# slave.net
KiCad netlist of a schematic drawn in EAGLE
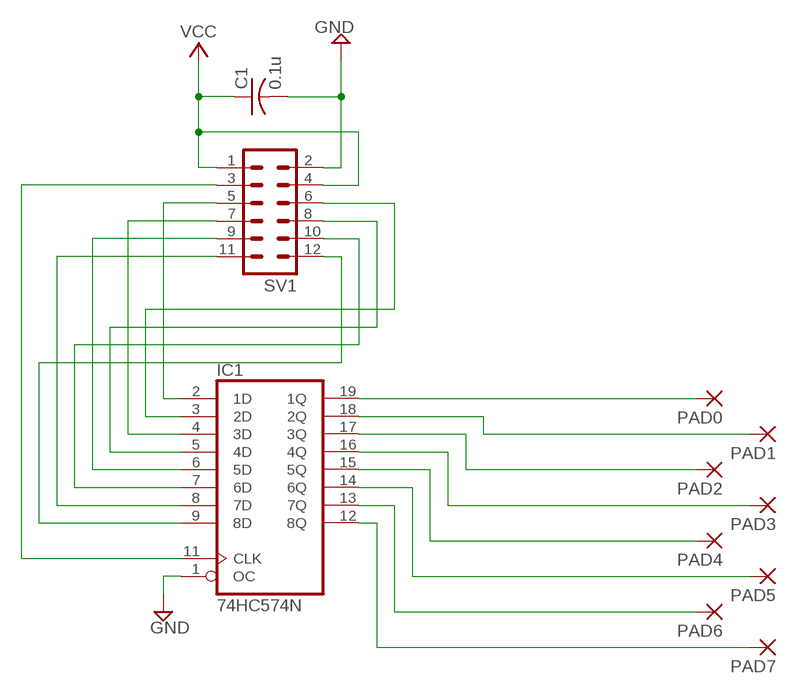
[diagram p0: schematic, sheet 1]

(export (version "E")
  (design (tool "Eeschema 10.0.6"))
  (components
    (comp (ref "C1")
      (value "0.1u")
      (footprint "eagle-import:C0805")
      (libsource (lib "eagle-import") (part "C-USC0805"))
    )
    (comp (ref "IC1")
      (value "74HC574N")
      (footprint "eagle-import:DIL20")
      (libsource (lib "eagle-import") (part "74574NHC"))
    )
    (comp (ref "PAD0")
      (value "2,54/0,8")
      (footprint "eagle-import:2,54_0,8")
      (libsource (lib "eagle-import") (part "2,54/0,8"))
    )
    (comp (ref "PAD1")
      (value "2,54/0,8")
      (footprint "eagle-import:2,54_0,8")
      (libsource (lib "eagle-import") (part "2,54/0,8"))
    )
    (comp (ref "PAD2")
      (value "2,54/0,8")
      (footprint "eagle-import:2,54_0,8")
      (libsource (lib "eagle-import") (part "2,54/0,8"))
    )
    (comp (ref "PAD3")
      (value "2,54/0,8")
      (footprint "eagle-import:2,54_0,8")
      (libsource (lib "eagle-import") (part "2,54/0,8"))
    )
    (comp (ref "PAD4")
      (value "2,54/0,8")
      (footprint "eagle-import:2,54_0,8")
      (libsource (lib "eagle-import") (part "2,54/0,8"))
    )
    (comp (ref "PAD5")
      (value "2,54/0,8")
      (footprint "eagle-import:2,54_0,8")
      (libsource (lib "eagle-import") (part "2,54/0,8"))
    )
    (comp (ref "PAD6")
      (value "2,54/0,8")
      (footprint "eagle-import:2,54_0,8")
      (libsource (lib "eagle-import") (part "2,54/0,8"))
    )
    (comp (ref "PAD7")
      (value "2,54/0,8")
      (footprint "eagle-import:2,54_0,8")
      (libsource (lib "eagle-import") (part "2,54/0,8"))
    )
    (comp (ref "SV1")
      (value "MA06-2")
      (footprint "eagle-import:MA06-2")
      (libsource (lib "eagle-import") (part "MA06-2"))
    )
  )
  (nets
    (net (code "1") (name "GND") (class "Default")
      (node (ref "C1") (pin "2") (pinfunction "2_2") (pintype "passive"))
      (node (ref "IC1") (pin "1") (pinfunction "OC_1") (pintype "input"))
      (node (ref "SV1") (pin "2") (pinfunction "2_2") (pintype "passive"))
    )
    (net (code "2") (name "Net-(IC1A-1D)") (class "Default")
      (node (ref "IC1") (pin "2") (pinfunction "1D_2") (pintype "input"))
      (node (ref "SV1") (pin "5") (pinfunction "5_5") (pintype "passive"))
    )
    (net (code "3") (name "Net-(IC1A-1Q)") (class "Default")
      (node (ref "IC1") (pin "19") (pinfunction "1Q_19") (pintype "tri_state"))
      (node (ref "PAD0") (pin "1") (pinfunction "P_1") (pintype "passive"))
    )
    (net (code "4") (name "Net-(IC1A-2D)") (class "Default")
      (node (ref "IC1") (pin "3") (pinfunction "2D_3") (pintype "input"))
      (node (ref "SV1") (pin "6") (pinfunction "6_6") (pintype "passive"))
    )
    (net (code "5") (name "Net-(IC1A-2Q)") (class "Default")
      (node (ref "IC1") (pin "18") (pinfunction "2Q_18") (pintype "tri_state"))
      (node (ref "PAD1") (pin "1") (pinfunction "P_1") (pintype "passive"))
    )
    (net (code "6") (name "Net-(IC1A-3D)") (class "Default")
      (node (ref "IC1") (pin "4") (pinfunction "3D_4") (pintype "input"))
      (node (ref "SV1") (pin "7") (pinfunction "7_7") (pintype "passive"))
    )
    (net (code "7") (name "Net-(IC1A-3Q)") (class "Default")
      (node (ref "IC1") (pin "17") (pinfunction "3Q_17") (pintype "tri_state"))
      (node (ref "PAD2") (pin "1") (pinfunction "P_1") (pintype "passive"))
    )
    (net (code "8") (name "Net-(IC1A-4D)") (class "Default")
      (node (ref "IC1") (pin "5") (pinfunction "4D_5") (pintype "input"))
      (node (ref "SV1") (pin "8") (pinfunction "8_8") (pintype "passive"))
    )
    (net (code "9") (name "Net-(IC1A-4Q)") (class "Default")
      (node (ref "IC1") (pin "16") (pinfunction "4Q_16") (pintype "tri_state"))
      (node (ref "PAD3") (pin "1") (pinfunction "P_1") (pintype "passive"))
    )
    (net (code "10") (name "Net-(IC1A-5D)") (class "Default")
      (node (ref "IC1") (pin "6") (pinfunction "5D_6") (pintype "input"))
      (node (ref "SV1") (pin "9") (pinfunction "9_9") (pintype "passive"))
    )
    (net (code "11") (name "Net-(IC1A-5Q)") (class "Default")
      (node (ref "IC1") (pin "15") (pinfunction "5Q_15") (pintype "tri_state"))
      (node (ref "PAD4") (pin "1") (pinfunction "P_1") (pintype "passive"))
    )
    (net (code "12") (name "Net-(IC1A-6D)") (class "Default")
      (node (ref "IC1") (pin "7") (pinfunction "6D_7") (pintype "input"))
      (node (ref "SV1") (pin "10") (pinfunction "10_10") (pintype "passive"))
    )
    (net (code "13") (name "Net-(IC1A-6Q)") (class "Default")
      (node (ref "IC1") (pin "14") (pinfunction "6Q_14") (pintype "tri_state"))
      (node (ref "PAD5") (pin "1") (pinfunction "P_1") (pintype "passive"))
    )
    (net (code "14") (name "Net-(IC1A-7D)") (class "Default")
      (node (ref "IC1") (pin "8") (pinfunction "7D_8") (pintype "input"))
      (node (ref "SV1") (pin "11") (pinfunction "11_11") (pintype "passive"))
    )
    (net (code "15") (name "Net-(IC1A-7Q)") (class "Default")
      (node (ref "IC1") (pin "13") (pinfunction "7Q_13") (pintype "tri_state"))
      (node (ref "PAD6") (pin "1") (pinfunction "P_1") (pintype "passive"))
    )
    (net (code "16") (name "Net-(IC1A-8D)") (class "Default")
      (node (ref "IC1") (pin "9") (pinfunction "8D_9") (pintype "input"))
      (node (ref "SV1") (pin "12") (pinfunction "12_12") (pintype "passive"))
    )
    (net (code "17") (name "Net-(IC1A-8Q)") (class "Default")
      (node (ref "IC1") (pin "12") (pinfunction "8Q_12") (pintype "tri_state"))
      (node (ref "PAD7") (pin "1") (pinfunction "P_1") (pintype "passive"))
    )
    (net (code "18") (name "Net-(IC1A-CLK)") (class "Default")
      (node (ref "IC1") (pin "11") (pinfunction "CLK_11") (pintype "input"))
      (node (ref "SV1") (pin "3") (pinfunction "3_3") (pintype "passive"))
    )
    (net (code "19") (name "VCC") (class "Default")
      (node (ref "C1") (pin "1") (pinfunction "1_1") (pintype "passive"))
      (node (ref "SV1") (pin "1") (pinfunction "1_1") (pintype "passive"))
      (node (ref "SV1") (pin "4") (pinfunction "4_4") (pintype "passive"))
    )
  )
)
